# keyboard.net
KiCad netlist of a schematic drawn in Altium Designer
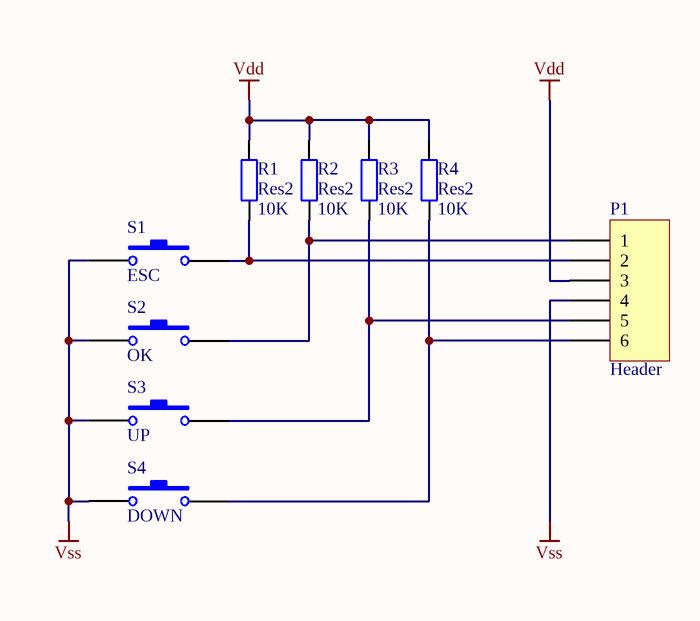
[diagram p0: keyboard.SchDoc]

(export (version "E")
  (design (tool "Eeschema 10.0.6"))
  (components
    (comp (ref "P1")
      (value "Header")
      (footprint "HDR1X6")
      (description "Header, 6-Pin")
      (fields (field (name "PUBLISHER") "Altium Limited"))
      (libsource (lib "Miscellaneous Connectors") (part "Header 6"))
    )
    (comp (ref "R1")
      (value "Res2")
      (footprint "0805")
      (description "Resistor")
      (fields (field (name "ALTIUM_VALUE") "10K") (field (name "PUBLISHER") "Altium Limited"))
      (libsource (lib "Miscellaneous Devices") (part "Res2"))
    )
    (comp (ref "R2")
      (value "Res2")
      (footprint "0805")
      (description "Resistor")
      (fields (field (name "ALTIUM_VALUE") "10K") (field (name "PUBLISHER") "Altium Limited"))
      (libsource (lib "Miscellaneous Devices") (part "Res2"))
    )
    (comp (ref "R3")
      (value "Res2")
      (footprint "0805")
      (description "Resistor")
      (fields (field (name "ALTIUM_VALUE") "10K") (field (name "PUBLISHER") "Altium Limited"))
      (libsource (lib "Miscellaneous Devices") (part "Res2"))
    )
    (comp (ref "R4")
      (value "Res2")
      (footprint "0805")
      (description "Resistor")
      (fields (field (name "ALTIUM_VALUE") "10K") (field (name "PUBLISHER") "Altium Limited"))
      (libsource (lib "Miscellaneous Devices") (part "Res2"))
    )
    (comp (ref "S1")
      (value "ESC")
      (footprint "Switch")
      (description "Switch")
      (fields (field (name "PUBLISHER") "Altium Limited"))
      (libsource (lib "Miscellaneous Devices") (part "SW-PB"))
    )
    (comp (ref "S2")
      (value "OK")
      (footprint "Switch")
      (description "Switch")
      (fields (field (name "PUBLISHER") "Altium Limited"))
      (libsource (lib "Miscellaneous Devices") (part "SW-PB"))
    )
    (comp (ref "S3")
      (value "UP")
      (footprint "Switch")
      (description "Switch")
      (fields (field (name "PUBLISHER") "Altium Limited"))
      (libsource (lib "Miscellaneous Devices") (part "SW-PB"))
    )
    (comp (ref "S4")
      (value "DOWN")
      (footprint "Switch")
      (description "Switch")
      (fields (field (name "PUBLISHER") "Altium Limited"))
      (libsource (lib "Miscellaneous Devices") (part "SW-PB"))
    )
  )
  (nets
    (net (code "1") (name "Net-(P1-Pad1)") (class "Default")
      (node (ref "P1") (pin "1") (pinfunction "1_1") (pintype "passive"))
      (node (ref "R2") (pin "1") (pinfunction "1_1") (pintype "passive"))
      (node (ref "S2") (pin "2") (pinfunction "2_2") (pintype "passive"))
    )
    (net (code "2") (name "Net-(P1-Pad2)") (class "Default")
      (node (ref "P1") (pin "2") (pinfunction "2_2") (pintype "passive"))
      (node (ref "R1") (pin "1") (pinfunction "1_1") (pintype "passive"))
      (node (ref "S1") (pin "2") (pinfunction "2_2") (pintype "passive"))
    )
    (net (code "3") (name "Net-(P1-Pad5)") (class "Default")
      (node (ref "P1") (pin "5") (pinfunction "5_5") (pintype "passive"))
      (node (ref "R3") (pin "1") (pinfunction "1_1") (pintype "passive"))
      (node (ref "S3") (pin "2") (pinfunction "2_2") (pintype "passive"))
    )
    (net (code "4") (name "Net-(P1-Pad6)") (class "Default")
      (node (ref "P1") (pin "6") (pinfunction "6_6") (pintype "passive"))
      (node (ref "R4") (pin "1") (pinfunction "1_1") (pintype "passive"))
      (node (ref "S4") (pin "2") (pinfunction "2_2") (pintype "passive"))
    )
    (net (code "5") (name "Vdd") (class "Default")
      (node (ref "P1") (pin "3") (pinfunction "3_3") (pintype "passive"))
      (node (ref "R1") (pin "2") (pinfunction "2_2") (pintype "passive"))
      (node (ref "R2") (pin "2") (pinfunction "2_2") (pintype "passive"))
      (node (ref "R3") (pin "2") (pinfunction "2_2") (pintype "passive"))
      (node (ref "R4") (pin "2") (pinfunction "2_2") (pintype "passive"))
    )
    (net (code "6") (name "Vss") (class "Default")
      (node (ref "P1") (pin "4") (pinfunction "4_4") (pintype "passive"))
      (node (ref "S1") (pin "1") (pinfunction "1_1") (pintype "passive"))
      (node (ref "S2") (pin "1") (pinfunction "1_1") (pintype "passive"))
      (node (ref "S3") (pin "1") (pinfunction "1_1") (pintype "passive"))
      (node (ref "S4") (pin "1") (pinfunction "1_1") (pintype "passive"))
    )
  )
)
